# esquema.net
KiCad netlist of a schematic drawn in EAGLE
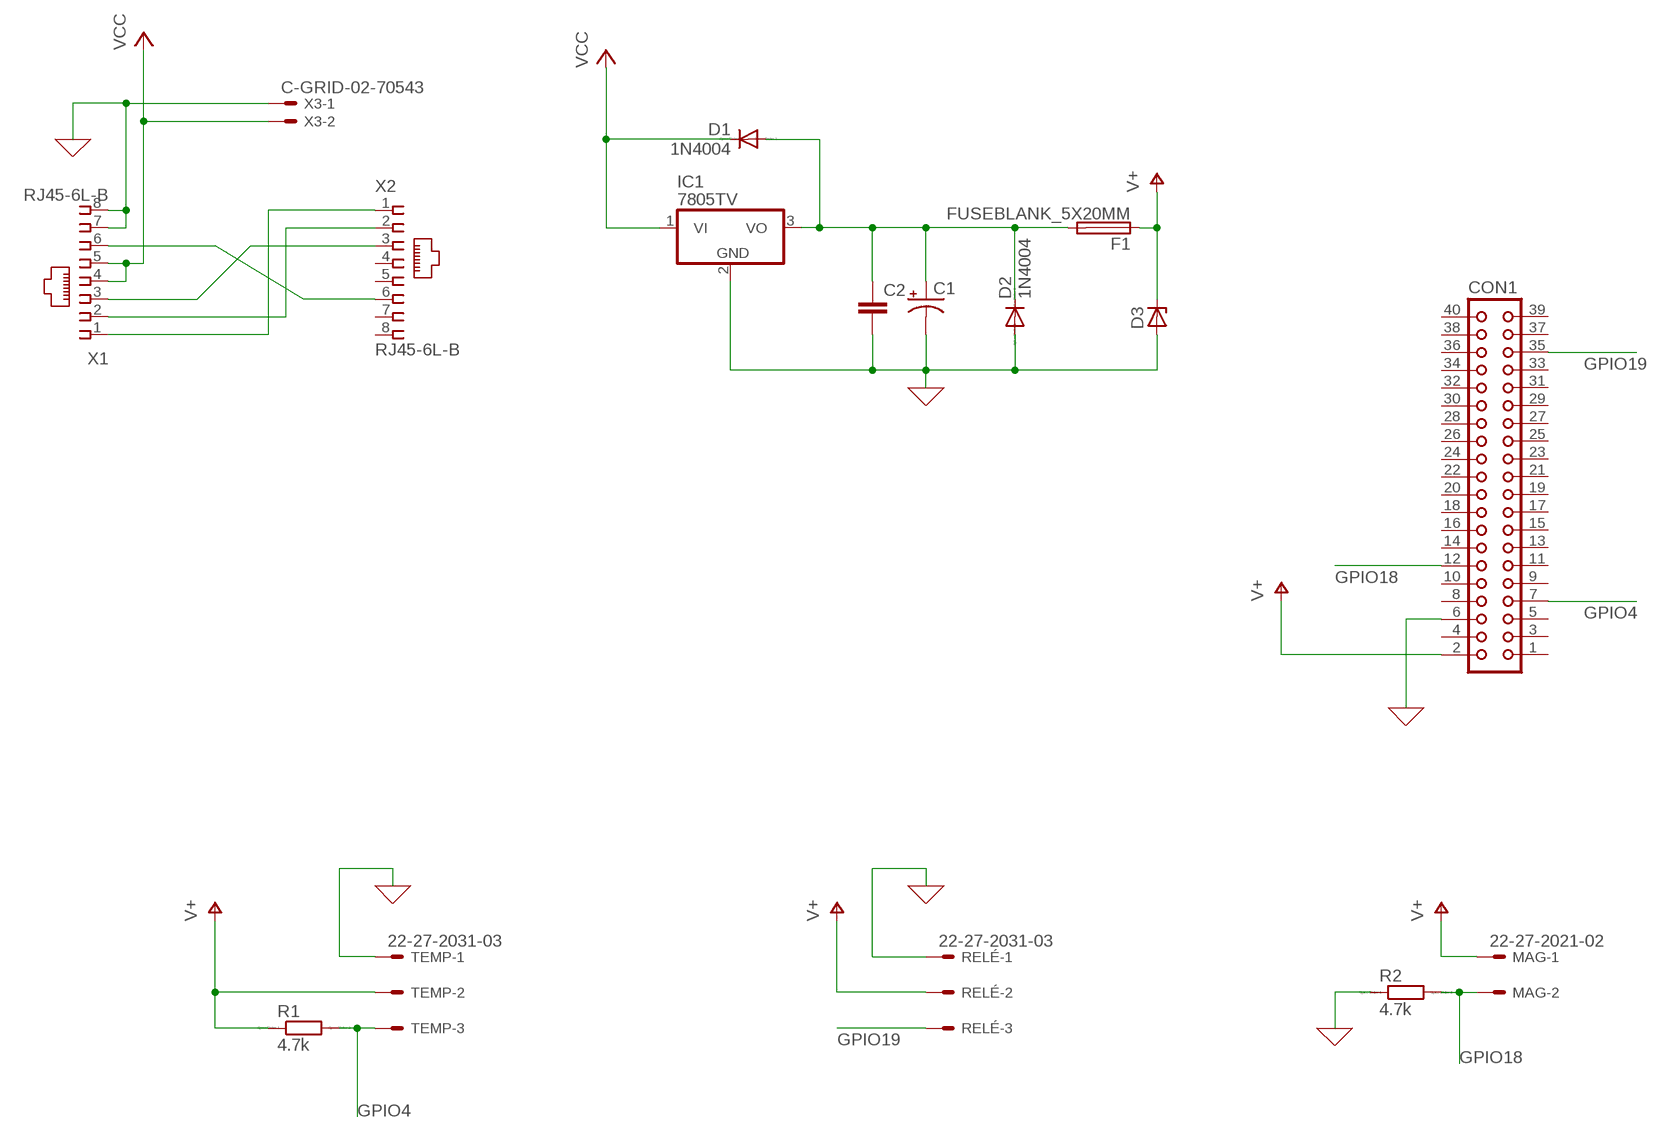
[diagram p0: schematic, sheet 1]

(export (version "E")
  (design (tool "Eeschema 10.0.6"))
  (components
    (comp (ref "C1")
      (value "CPOL-USE5-8.5")
      (footprint "eagle-import:E5-8,5")
      (libsource (lib "eagle-import") (part "CPOL-USE5-8.5"))
    )
    (comp (ref "C2")
      (value "C-EU025-030X050")
      (footprint "eagle-import:C025-030X050")
      (libsource (lib "eagle-import") (part "C-EU025-030X050"))
    )
    (comp (ref "CON1")
      (value "CON40")
      (footprint "eagle-import:CON40")
      (libsource (lib "eagle-import") (part "CON40"))
    )
    (comp (ref "D1")
      (value "1N4004")
      (footprint "eagle-import:DO41-10")
      (libsource (lib "eagle-import") (part "1N4004"))
    )
    (comp (ref "D2")
      (value "1N4004")
      (footprint "eagle-import:DO41-10")
      (libsource (lib "eagle-import") (part "1N4004"))
    )
    (comp (ref "D3")
      (value "ZENER-DIODEDO35Z10")
      (footprint "eagle-import:DO35Z10")
      (libsource (lib "eagle-import") (part "ZENER-DIODEDO35Z10"))
    )
    (comp (ref "F1")
      (value "FUSEBLANK_5X20MM")
      (footprint "eagle-import:FUSE_HOLDER_5X20MM")
      (libsource (lib "eagle-import") (part "FUSEBLANK_5X20MM"))
    )
    (comp (ref "IC1")
      (value "7805TV")
      (footprint "eagle-import:TO220V")
      (libsource (lib "eagle-import") (part "78TV05"))
    )
    (comp (ref "MAG")
      (value "22-27-2021-02")
      (footprint "eagle-import:6410-02")
      (fields (field (name "MF") "MOLEX"))
      (libsource (lib "eagle-import") (part "22-?-0227-2021"))
    )
    (comp (ref "R1")
      (value "4.7k")
      (footprint "eagle-import:0204_7")
      (libsource (lib "eagle-import") (part "R0204/7"))
    )
    (comp (ref "R2")
      (value "4.7k")
      (footprint "eagle-import:0204_7")
      (libsource (lib "eagle-import") (part "R0204/7"))
    )
    (comp (ref "RELÉ")
      (value "22-27-2031-03")
      (footprint "eagle-import:6410-03")
      (fields (field (name "MF") "MOLEX"))
      (libsource (lib "eagle-import") (part "22-?-0327-2031"))
    )
    (comp (ref "TEMP")
      (value "22-27-2031-03")
      (footprint "eagle-import:6410-03")
      (fields (field (name "MF") "MOLEX"))
      (libsource (lib "eagle-import") (part "22-?-0327-2031"))
    )
    (comp (ref "X1")
      (value "RJ45-6L-B")
      (footprint "eagle-import:RJ45-NO-SHIELD")
      (libsource (lib "eagle-import") (part "RJ45-6L-B"))
    )
    (comp (ref "X2")
      (value "RJ45-6L-B")
      (footprint "eagle-import:RJ45-NO-SHIELD")
      (libsource (lib "eagle-import") (part "RJ45-6L-B"))
    )
    (comp (ref "X3")
      (value "C-GRID-02-70543")
      (footprint "eagle-import:70543-02")
      (fields (field (name "MF") "MOLEX"))
      (libsource (lib "eagle-import") (part "C-GRID-02-70543"))
    )
  )
  (nets
    (net (code "1") (name "/GPIO4") (class "Default")
      (node (ref "CON1") (pin "7") (pinfunction "7_7") (pintype "passive"))
      (node (ref "R1") (pin "2") (pinfunction "2_2") (pintype "passive"))
      (node (ref "TEMP") (pin "3") (pinfunction "S_3") (pintype "passive"))
    )
    (net (code "2") (name "/GPIO18") (class "Default")
      (node (ref "CON1") (pin "12") (pinfunction "12_12") (pintype "passive"))
      (node (ref "MAG") (pin "2") (pinfunction "S_2") (pintype "passive"))
      (node (ref "R2") (pin "2") (pinfunction "2_2") (pintype "passive"))
    )
    (net (code "3") (name "/GPIO19") (class "Default")
      (node (ref "CON1") (pin "35") (pinfunction "35_35") (pintype "passive"))
      (node (ref "RELÉ") (pin "3") (pinfunction "S_3") (pintype "passive"))
    )
    (net (code "4") (name "GND") (class "Default")
      (node (ref "C1") (pin "-") (pinfunction "-_-") (pintype "passive"))
      (node (ref "C2") (pin "2") (pinfunction "2_2") (pintype "passive"))
      (node (ref "CON1") (pin "6") (pinfunction "6_6") (pintype "passive"))
      (node (ref "D2") (pin "A") (pinfunction "A_A") (pintype "passive"))
      (node (ref "D3") (pin "A") (pinfunction "A_A") (pintype "passive"))
      (node (ref "IC1") (pin "2") (pinfunction "GND_2") (pintype "passive"))
      (node (ref "R2") (pin "1") (pinfunction "1_1") (pintype "passive"))
      (node (ref "RELÉ") (pin "1") (pinfunction "S_1") (pintype "passive"))
      (node (ref "TEMP") (pin "1") (pinfunction "S_1") (pintype "passive"))
      (node (ref "X1") (pin "7") (pinfunction "7_7") (pintype "passive"))
      (node (ref "X1") (pin "8") (pinfunction "8_8") (pintype "passive"))
      (node (ref "X3") (pin "1") (pinfunction "S_1") (pintype "passive"))
    )
    (net (code "5") (name "Net-(IC1-VO)") (class "Default")
      (node (ref "C1") (pin "+") (pinfunction "+_+") (pintype "passive"))
      (node (ref "C2") (pin "1") (pinfunction "1_1") (pintype "passive"))
      (node (ref "D1") (pin "A") (pinfunction "A_A") (pintype "passive"))
      (node (ref "D2") (pin "C") (pinfunction "C_C") (pintype "passive"))
      (node (ref "F1") (pin "2") (pinfunction "2_2") (pintype "passive"))
      (node (ref "IC1") (pin "3") (pinfunction "VO_3") (pintype "passive"))
    )
    (net (code "6") (name "Net-(X1-Pad1)") (class "Default")
      (node (ref "X1") (pin "1") (pinfunction "1_1") (pintype "passive"))
      (node (ref "X2") (pin "1") (pinfunction "1_1") (pintype "passive"))
    )
    (net (code "7") (name "Net-(X1-Pad2)") (class "Default")
      (node (ref "X1") (pin "2") (pinfunction "2_2") (pintype "passive"))
      (node (ref "X2") (pin "2") (pinfunction "2_2") (pintype "passive"))
    )
    (net (code "8") (name "Net-(X1-Pad3)") (class "Default")
      (node (ref "X1") (pin "3") (pinfunction "3_3") (pintype "passive"))
      (node (ref "X2") (pin "3") (pinfunction "3_3") (pintype "passive"))
    )
    (net (code "9") (name "Net-(X1-Pad6)") (class "Default")
      (node (ref "X1") (pin "6") (pinfunction "6_6") (pintype "passive"))
      (node (ref "X2") (pin "6") (pinfunction "6_6") (pintype "passive"))
    )
    (net (code "10") (name "V+") (class "Default")
      (node (ref "CON1") (pin "2") (pinfunction "2_2") (pintype "passive"))
      (node (ref "D3") (pin "C") (pinfunction "C_C") (pintype "passive"))
      (node (ref "F1") (pin "1") (pinfunction "1_1") (pintype "passive"))
      (node (ref "MAG") (pin "1") (pinfunction "S_1") (pintype "passive"))
      (node (ref "R1") (pin "1") (pinfunction "1_1") (pintype "passive"))
      (node (ref "RELÉ") (pin "2") (pinfunction "S_2") (pintype "passive"))
      (node (ref "TEMP") (pin "2") (pinfunction "S_2") (pintype "passive"))
    )
    (net (code "11") (name "VCC") (class "Default")
      (node (ref "D1") (pin "C") (pinfunction "C_C") (pintype "passive"))
      (node (ref "IC1") (pin "1") (pinfunction "VI_1") (pintype "input"))
      (node (ref "X1") (pin "4") (pinfunction "4_4") (pintype "passive"))
      (node (ref "X1") (pin "5") (pinfunction "5_5") (pintype "passive"))
      (node (ref "X3") (pin "2") (pinfunction "S_2") (pintype "passive"))
    )
    (net (code "12") (name "unconnected-(CON1-Pad1)") (class "Default")
      (node (ref "CON1") (pin "1") (pinfunction "1_1") (pintype "passive"))
    )
    (net (code "13") (name "unconnected-(CON1-Pad3)") (class "Default")
      (node (ref "CON1") (pin "3") (pinfunction "3_3") (pintype "passive"))
    )
    (net (code "14") (name "unconnected-(CON1-Pad4)") (class "Default")
      (node (ref "CON1") (pin "4") (pinfunction "4_4") (pintype "passive"))
    )
    (net (code "15") (name "unconnected-(CON1-Pad5)") (class "Default")
      (node (ref "CON1") (pin "5") (pinfunction "5_5") (pintype "passive"))
    )
    (net (code "16") (name "unconnected-(CON1-Pad8)") (class "Default")
      (node (ref "CON1") (pin "8") (pinfunction "8_8") (pintype "passive"))
    )
    (net (code "17") (name "unconnected-(CON1-Pad9)") (class "Default")
      (node (ref "CON1") (pin "9") (pinfunction "9_9") (pintype "passive"))
    )
    (net (code "18") (name "unconnected-(CON1-Pad10)") (class "Default")
      (node (ref "CON1") (pin "10") (pinfunction "10_10") (pintype "passive"))
    )
    (net (code "19") (name "unconnected-(CON1-Pad11)") (class "Default")
      (node (ref "CON1") (pin "11") (pinfunction "11_11") (pintype "passive"))
    )
    (net (code "20") (name "unconnected-(CON1-Pad13)") (class "Default")
      (node (ref "CON1") (pin "13") (pinfunction "13_13") (pintype "passive"))
    )
    (net (code "21") (name "unconnected-(CON1-Pad14)") (class "Default")
      (node (ref "CON1") (pin "14") (pinfunction "14_14") (pintype "passive"))
    )
    (net (code "22") (name "unconnected-(CON1-Pad15)") (class "Default")
      (node (ref "CON1") (pin "15") (pinfunction "15_15") (pintype "passive"))
    )
    (net (code "23") (name "unconnected-(CON1-Pad16)") (class "Default")
      (node (ref "CON1") (pin "16") (pinfunction "16_16") (pintype "passive"))
    )
    (net (code "24") (name "unconnected-(CON1-Pad17)") (class "Default")
      (node (ref "CON1") (pin "17") (pinfunction "17_17") (pintype "passive"))
    )
    (net (code "25") (name "unconnected-(CON1-Pad18)") (class "Default")
      (node (ref "CON1") (pin "18") (pinfunction "18_18") (pintype "passive"))
    )
    (net (code "26") (name "unconnected-(CON1-Pad19)") (class "Default")
      (node (ref "CON1") (pin "19") (pinfunction "19_19") (pintype "passive"))
    )
    (net (code "27") (name "unconnected-(CON1-Pad20)") (class "Default")
      (node (ref "CON1") (pin "20") (pinfunction "20_20") (pintype "passive"))
    )
    (net (code "28") (name "unconnected-(CON1-Pad21)") (class "Default")
      (node (ref "CON1") (pin "21") (pinfunction "21_21") (pintype "passive"))
    )
    (net (code "29") (name "unconnected-(CON1-Pad22)") (class "Default")
      (node (ref "CON1") (pin "22") (pinfunction "22_22") (pintype "passive"))
    )
    (net (code "30") (name "unconnected-(CON1-Pad23)") (class "Default")
      (node (ref "CON1") (pin "23") (pinfunction "23_23") (pintype "passive"))
    )
    (net (code "31") (name "unconnected-(CON1-Pad24)") (class "Default")
      (node (ref "CON1") (pin "24") (pinfunction "24_24") (pintype "passive"))
    )
    (net (code "32") (name "unconnected-(CON1-Pad25)") (class "Default")
      (node (ref "CON1") (pin "25") (pinfunction "25_25") (pintype "passive"))
    )
    (net (code "33") (name "unconnected-(CON1-Pad26)") (class "Default")
      (node (ref "CON1") (pin "26") (pinfunction "26_26") (pintype "passive"))
    )
    (net (code "34") (name "unconnected-(CON1-Pad27)") (class "Default")
      (node (ref "CON1") (pin "27") (pinfunction "27_27") (pintype "passive"))
    )
    (net (code "35") (name "unconnected-(CON1-Pad28)") (class "Default")
      (node (ref "CON1") (pin "28") (pinfunction "28_28") (pintype "passive"))
    )
    (net (code "36") (name "unconnected-(CON1-Pad29)") (class "Default")
      (node (ref "CON1") (pin "29") (pinfunction "29_29") (pintype "passive"))
    )
    (net (code "37") (name "unconnected-(CON1-Pad30)") (class "Default")
      (node (ref "CON1") (pin "30") (pinfunction "30_30") (pintype "passive"))
    )
    (net (code "38") (name "unconnected-(CON1-Pad31)") (class "Default")
      (node (ref "CON1") (pin "31") (pinfunction "31_31") (pintype "passive"))
    )
    (net (code "39") (name "unconnected-(CON1-Pad32)") (class "Default")
      (node (ref "CON1") (pin "32") (pinfunction "32_32") (pintype "passive"))
    )
    (net (code "40") (name "unconnected-(CON1-Pad33)") (class "Default")
      (node (ref "CON1") (pin "33") (pinfunction "33_33") (pintype "passive"))
    )
    (net (code "41") (name "unconnected-(CON1-Pad34)") (class "Default")
      (node (ref "CON1") (pin "34") (pinfunction "34_34") (pintype "passive"))
    )
    (net (code "42") (name "unconnected-(CON1-Pad36)") (class "Default")
      (node (ref "CON1") (pin "36") (pinfunction "36_36") (pintype "passive"))
    )
    (net (code "43") (name "unconnected-(CON1-Pad37)") (class "Default")
      (node (ref "CON1") (pin "37") (pinfunction "37_37") (pintype "passive"))
    )
    (net (code "44") (name "unconnected-(CON1-Pad38)") (class "Default")
      (node (ref "CON1") (pin "38") (pinfunction "38_38") (pintype "passive"))
    )
    (net (code "45") (name "unconnected-(CON1-Pad39)") (class "Default")
      (node (ref "CON1") (pin "39") (pinfunction "39_39") (pintype "passive"))
    )
    (net (code "46") (name "unconnected-(CON1-Pad40)") (class "Default")
      (node (ref "CON1") (pin "40") (pinfunction "40_40") (pintype "passive"))
    )
    (net (code "47") (name "unconnected-(X2-Pad4)") (class "Default")
      (node (ref "X2") (pin "4") (pinfunction "4_4") (pintype "passive"))
    )
    (net (code "48") (name "unconnected-(X2-Pad5)") (class "Default")
      (node (ref "X2") (pin "5") (pinfunction "5_5") (pintype "passive"))
    )
    (net (code "49") (name "unconnected-(X2-Pad7)") (class "Default")
      (node (ref "X2") (pin "7") (pinfunction "7_7") (pintype "passive"))
    )
    (net (code "50") (name "unconnected-(X2-Pad8)") (class "Default")
      (node (ref "X2") (pin "8") (pinfunction "8_8") (pintype "passive"))
    )
  )
)
